# Sensores.net
KiCad netlist of a schematic drawn in Altium Designer
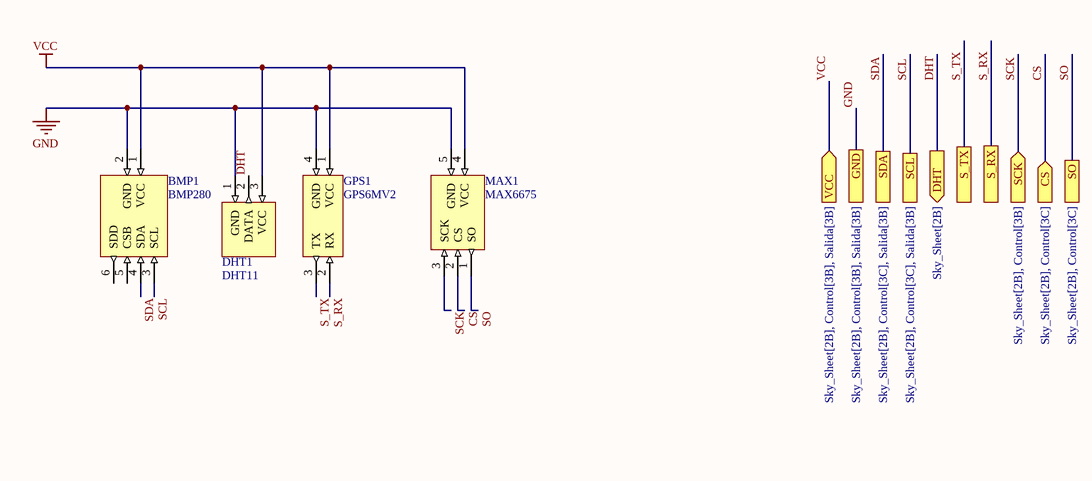
[diagram p0: Sensores.SchDoc]

(export (version "E")
  (design (tool "Eeschema 10.0.6"))
  (components
    (comp (ref "BMP1") (value "BMP280") (footprint "BMP280") (libsource (lib "Sky_Schlib") (part "BMP280")))
    (comp (ref "DHT1") (value "DHT11") (footprint "DHT11") (libsource (lib "Sky_Schlib") (part "DHT11")))
    (comp (ref "GPS1") (value "GPS6MV2") (footprint "GPS") (libsource (lib "Sky_Schlib") (part "GPS6MV2")))
    (comp (ref "MAX1")
      (value "MAX6675")
      (footprint "MAX6675")
      (libsource (lib "Sky_Schlib") (part "MAX6675"))
    )
  )
  (nets
    (net (code "1") (name "/CS") (class "Default")
      (node (ref "MAX1") (pin "2") (pinfunction "CS_2") (pintype "input"))
    )
    (net (code "2") (name "/DHT") (class "Default")
      (node (ref "DHT1") (pin "2") (pinfunction "DATA_2") (pintype "output"))
    )
    (net (code "3") (name "/SCK") (class "Default")
      (node (ref "MAX1") (pin "3") (pinfunction "SCK_3") (pintype "input"))
    )
    (net (code "4") (name "/SCL") (class "Default")
      (node (ref "BMP1") (pin "3") (pinfunction "SCL_3") (pintype "input"))
    )
    (net (code "5") (name "/SDA") (class "Default")
      (node (ref "BMP1") (pin "4") (pinfunction "SDA_4") (pintype "input"))
    )
    (net (code "6") (name "/SO") (class "Default")
      (node (ref "MAX1") (pin "1") (pinfunction "SO_1") (pintype "output"))
    )
    (net (code "7") (name "/S_RX") (class "Default")
      (node (ref "GPS1") (pin "2") (pinfunction "RX_2") (pintype "input"))
    )
    (net (code "8") (name "/S_TX") (class "Default")
      (node (ref "GPS1") (pin "3") (pinfunction "TX_3") (pintype "output"))
    )
    (net (code "9") (name "GND") (class "Default")
      (node (ref "BMP1") (pin "2") (pinfunction "GND_2") (pintype "input"))
      (node (ref "DHT1") (pin "1") (pinfunction "GND_1") (pintype "input"))
      (node (ref "GPS1") (pin "4") (pinfunction "GND_4") (pintype "input"))
      (node (ref "MAX1") (pin "5") (pinfunction "GND_5") (pintype "input"))
    )
    (net (code "10") (name "VCC") (class "Default")
      (node (ref "BMP1") (pin "1") (pinfunction "VCC_1") (pintype "input"))
      (node (ref "DHT1") (pin "3") (pinfunction "VCC_3") (pintype "input"))
      (node (ref "GPS1") (pin "1") (pinfunction "VCC_1") (pintype "input"))
      (node (ref "MAX1") (pin "4") (pinfunction "VCC_4") (pintype "input"))
    )
    (net (code "11") (name "unconnected-(BMP1-CSB-Pad5)") (class "Default")
      (node (ref "BMP1") (pin "5") (pinfunction "CSB_5") (pintype "input"))
    )
    (net (code "12") (name "unconnected-(BMP1-SDD-Pad6)") (class "Default")
      (node (ref "BMP1") (pin "6") (pinfunction "SDD_6") (pintype "output"))
    )
  )
)
